# Power.net
KiCad netlist of a schematic drawn in Altium Designer
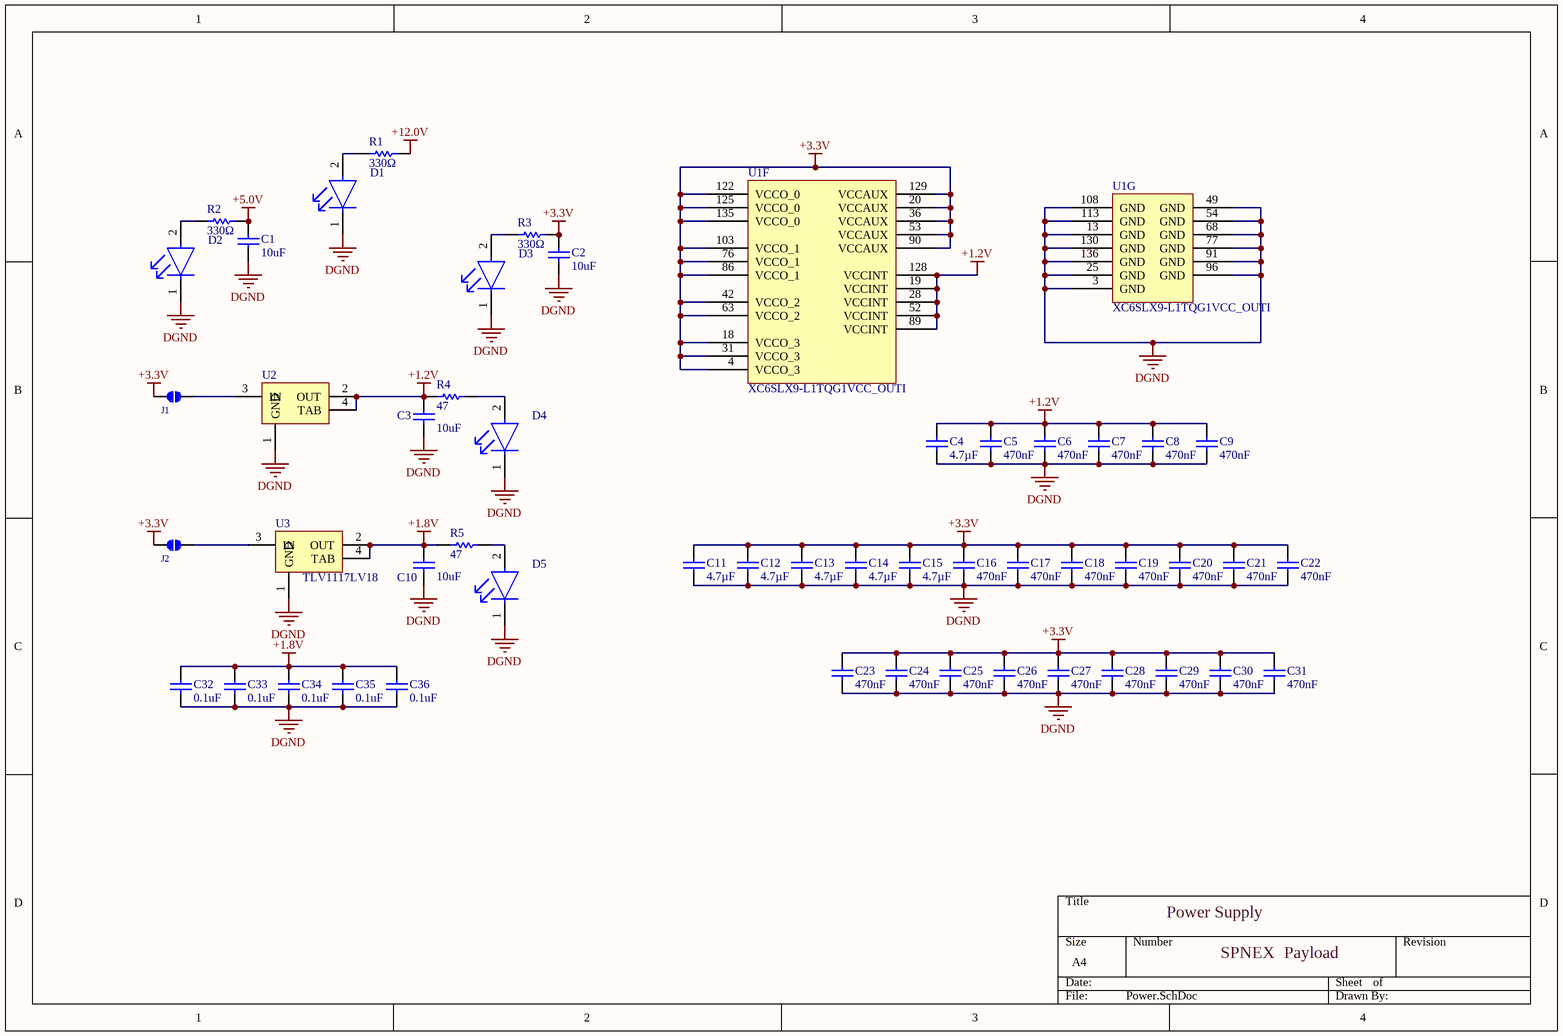
[diagram p0: Power.SchDoc]

(export (version "E")
  (design (tool "Eeschema 10.0.6"))
  (components
    (comp (ref "C1")
      (value "10uF")
      (footprint "capc3216n")
      (description "Capacitor")
      (fields (field (name "Comment") "Cap Semi"))
      (libsource (lib "SPNeX_NewPL") (part "Cap_CER_10U_10V_1206"))
    )
    (comp (ref "C2")
      (value "10uF")
      (footprint "capc3216n")
      (description "Capacitor")
      (fields (field (name "Comment") "Cap Semi"))
      (libsource (lib "SPNeX_NewPL") (part "Cap_CER_10U_10V_1206"))
    )
    (comp (ref "C3")
      (value "10uF")
      (footprint "capc3216n")
      (description "Capacitor")
      (fields (field (name "Comment") "Cap Semi"))
      (libsource (lib "SPNeX_NewPL") (part "Cap_CER_10U_10V_1206"))
    )
    (comp (ref "C4")
      (value "Cap_CER_4.7U_25V_0805")
      (footprint "0805CAP")
      (description "CAP CER 4.7UF 25V X7R 0805")
      (fields
        (field (name "MANUFACTURER") "TDK Corporation")
        (field (name "MANUFACTURER PART NUMBER") "C2012X7R1E475K125AB")
        (field (name "CAPACITANCE") "4.7µF")
      )
      (libsource (lib "SPNeX_NewPL") (part "Cap_CER_4.7U_25V_0805"))
    )
    (comp (ref "C5")
      (value "CAP CER 0.47UF 10V X7R 0603")
      (footprint "0603CAP")
      (description "0.47µF ±10% 10V Ceramic Capacitor X7R 0603 (1608 Metric)")
      (fields
        (field (name "MANUFACTURER") "KEMET")
        (field (name "MANUFACTURER PART NUMBER") "C0603C474K8RACTU")
        (field (name "CAPACITANCE") "470nF")
      )
      (libsource (lib "SPNeX_NewPL") (part "Cap_CER_0.47U_10V_0603"))
    )
    (comp (ref "C6")
      (value "CAP CER 0.47UF 10V X7R 0603")
      (footprint "0603CAP")
      (description "0.47µF ±10% 10V Ceramic Capacitor X7R 0603 (1608 Metric)")
      (fields
        (field (name "MANUFACTURER") "KEMET")
        (field (name "MANUFACTURER PART NUMBER") "C0603C474K8RACTU")
        (field (name "CAPACITANCE") "470nF")
      )
      (libsource (lib "SPNeX_NewPL") (part "Cap_CER_0.47U_10V_0603"))
    )
    (comp (ref "C7")
      (value "CAP CER 0.47UF 10V X7R 0603")
      (footprint "0603CAP")
      (description "0.47µF ±10% 10V Ceramic Capacitor X7R 0603 (1608 Metric)")
      (fields
        (field (name "MANUFACTURER") "KEMET")
        (field (name "MANUFACTURER PART NUMBER") "C0603C474K8RACTU")
        (field (name "CAPACITANCE") "470nF")
      )
      (libsource (lib "SPNeX_NewPL") (part "Cap_CER_0.47U_10V_0603"))
    )
    (comp (ref "C8")
      (value "CAP CER 0.47UF 10V X7R 0603")
      (footprint "0603CAP")
      (description "0.47µF ±10% 10V Ceramic Capacitor X7R 0603 (1608 Metric)")
      (fields
        (field (name "MANUFACTURER") "KEMET")
        (field (name "MANUFACTURER PART NUMBER") "C0603C474K8RACTU")
        (field (name "CAPACITANCE") "470nF")
      )
      (libsource (lib "SPNeX_NewPL") (part "Cap_CER_0.47U_10V_0603"))
    )
    (comp (ref "C9")
      (value "CAP CER 0.47UF 10V X7R 0603")
      (footprint "0603CAP")
      (description "0.47µF ±10% 10V Ceramic Capacitor X7R 0603 (1608 Metric)")
      (fields
        (field (name "MANUFACTURER") "KEMET")
        (field (name "MANUFACTURER PART NUMBER") "C0603C474K8RACTU")
        (field (name "CAPACITANCE") "470nF")
      )
      (libsource (lib "SPNeX_NewPL") (part "Cap_CER_0.47U_10V_0603"))
    )
    (comp (ref "C10")
      (value "10uF")
      (footprint "capc3216n")
      (description "Capacitor")
      (fields (field (name "Comment") "Cap Semi"))
      (libsource (lib "SPNeX_NewPL") (part "Cap_CER_10U_10V_1206"))
    )
    (comp (ref "C11")
      (value "Cap_CER_4.7U_25V_0805")
      (footprint "0805CAP")
      (description "CAP CER 4.7UF 25V X7R 0805")
      (fields
        (field (name "MANUFACTURER") "TDK Corporation")
        (field (name "MANUFACTURER PART NUMBER") "C2012X7R1E475K125AB")
        (field (name "CAPACITANCE") "4.7µF")
      )
      (libsource (lib "SPNeX_NewPL") (part "Cap_CER_4.7U_25V_0805"))
    )
    (comp (ref "C12")
      (value "Cap_CER_4.7U_25V_0805")
      (footprint "0805CAP")
      (description "CAP CER 4.7UF 25V X7R 0805")
      (fields
        (field (name "MANUFACTURER") "TDK Corporation")
        (field (name "MANUFACTURER PART NUMBER") "C2012X7R1E475K125AB")
        (field (name "CAPACITANCE") "4.7µF")
      )
      (libsource (lib "SPNeX_NewPL") (part "Cap_CER_4.7U_25V_0805"))
    )
    (comp (ref "C13")
      (value "Cap_CER_4.7U_25V_0805")
      (footprint "0805CAP")
      (description "CAP CER 4.7UF 25V X7R 0805")
      (fields
        (field (name "MANUFACTURER") "TDK Corporation")
        (field (name "MANUFACTURER PART NUMBER") "C2012X7R1E475K125AB")
        (field (name "CAPACITANCE") "4.7µF")
      )
      (libsource (lib "SPNeX_NewPL") (part "Cap_CER_4.7U_25V_0805"))
    )
    (comp (ref "C14")
      (value "Cap_CER_4.7U_25V_0805")
      (footprint "0805CAP")
      (description "CAP CER 4.7UF 25V X7R 0805")
      (fields
        (field (name "MANUFACTURER") "TDK Corporation")
        (field (name "MANUFACTURER PART NUMBER") "C2012X7R1E475K125AB")
        (field (name "CAPACITANCE") "4.7µF")
      )
      (libsource (lib "SPNeX_NewPL") (part "Cap_CER_4.7U_25V_0805"))
    )
    (comp (ref "C15")
      (value "Cap_CER_4.7U_25V_0805")
      (footprint "0805CAP")
      (description "CAP CER 4.7UF 25V X7R 0805")
      (fields
        (field (name "MANUFACTURER") "TDK Corporation")
        (field (name "MANUFACTURER PART NUMBER") "C2012X7R1E475K125AB")
        (field (name "CAPACITANCE") "4.7µF")
      )
      (libsource (lib "SPNeX_NewPL") (part "Cap_CER_4.7U_25V_0805"))
    )
    (comp (ref "C16")
      (value "CAP CER 0.47UF 10V X7R 0603")
      (footprint "0603CAP")
      (description "0.47µF ±10% 10V Ceramic Capacitor X7R 0603 (1608 Metric)")
      (fields
        (field (name "MANUFACTURER") "KEMET")
        (field (name "MANUFACTURER PART NUMBER") "C0603C474K8RACTU")
        (field (name "CAPACITANCE") "470nF")
      )
      (libsource (lib "SPNeX_NewPL") (part "Cap_CER_0.47U_10V_0603"))
    )
    (comp (ref "C17")
      (value "CAP CER 0.47UF 10V X7R 0603")
      (footprint "0603CAP")
      (description "0.47µF ±10% 10V Ceramic Capacitor X7R 0603 (1608 Metric)")
      (fields
        (field (name "MANUFACTURER") "KEMET")
        (field (name "MANUFACTURER PART NUMBER") "C0603C474K8RACTU")
        (field (name "CAPACITANCE") "470nF")
      )
      (libsource (lib "SPNeX_NewPL") (part "Cap_CER_0.47U_10V_0603"))
    )
    (comp (ref "C18")
      (value "CAP CER 0.47UF 10V X7R 0603")
      (footprint "0603CAP")
      (description "0.47µF ±10% 10V Ceramic Capacitor X7R 0603 (1608 Metric)")
      (fields
        (field (name "MANUFACTURER") "KEMET")
        (field (name "MANUFACTURER PART NUMBER") "C0603C474K8RACTU")
        (field (name "CAPACITANCE") "470nF")
      )
      (libsource (lib "SPNeX_NewPL") (part "Cap_CER_0.47U_10V_0603"))
    )
    (comp (ref "C19")
      (value "CAP CER 0.47UF 10V X7R 0603")
      (footprint "0603CAP")
      (description "0.47µF ±10% 10V Ceramic Capacitor X7R 0603 (1608 Metric)")
      (fields
        (field (name "MANUFACTURER") "KEMET")
        (field (name "MANUFACTURER PART NUMBER") "C0603C474K8RACTU")
        (field (name "CAPACITANCE") "470nF")
      )
      (libsource (lib "SPNeX_NewPL") (part "Cap_CER_0.47U_10V_0603"))
    )
    (comp (ref "C20")
      (value "CAP CER 0.47UF 10V X7R 0603")
      (footprint "0603CAP")
      (description "0.47µF ±10% 10V Ceramic Capacitor X7R 0603 (1608 Metric)")
      (fields
        (field (name "MANUFACTURER") "KEMET")
        (field (name "MANUFACTURER PART NUMBER") "C0603C474K8RACTU")
        (field (name "CAPACITANCE") "470nF")
      )
      (libsource (lib "SPNeX_NewPL") (part "Cap_CER_0.47U_10V_0603"))
    )
    (comp (ref "C21")
      (value "CAP CER 0.47UF 10V X7R 0603")
      (footprint "0603CAP")
      (description "0.47µF ±10% 10V Ceramic Capacitor X7R 0603 (1608 Metric)")
      (fields
        (field (name "MANUFACTURER") "KEMET")
        (field (name "MANUFACTURER PART NUMBER") "C0603C474K8RACTU")
        (field (name "CAPACITANCE") "470nF")
      )
      (libsource (lib "SPNeX_NewPL") (part "Cap_CER_0.47U_10V_0603"))
    )
    (comp (ref "C22")
      (value "CAP CER 0.47UF 10V X7R 0603")
      (footprint "0603CAP")
      (description "0.47µF ±10% 10V Ceramic Capacitor X7R 0603 (1608 Metric)")
      (fields
        (field (name "MANUFACTURER") "KEMET")
        (field (name "MANUFACTURER PART NUMBER") "C0603C474K8RACTU")
        (field (name "CAPACITANCE") "470nF")
      )
      (libsource (lib "SPNeX_NewPL") (part "Cap_CER_0.47U_10V_0603"))
    )
    (comp (ref "C23")
      (value "CAP CER 0.47UF 10V X7R 0603")
      (footprint "0603CAP")
      (description "0.47µF ±10% 10V Ceramic Capacitor X7R 0603 (1608 Metric)")
      (fields
        (field (name "MANUFACTURER") "KEMET")
        (field (name "MANUFACTURER PART NUMBER") "C0603C474K8RACTU")
        (field (name "CAPACITANCE") "470nF")
      )
      (libsource (lib "SPNeX_NewPL") (part "Cap_CER_0.47U_10V_0603"))
    )
    (comp (ref "C24")
      (value "CAP CER 0.47UF 10V X7R 0603")
      (footprint "0603CAP")
      (description "0.47µF ±10% 10V Ceramic Capacitor X7R 0603 (1608 Metric)")
      (fields
        (field (name "MANUFACTURER") "KEMET")
        (field (name "MANUFACTURER PART NUMBER") "C0603C474K8RACTU")
        (field (name "CAPACITANCE") "470nF")
      )
      (libsource (lib "SPNeX_NewPL") (part "Cap_CER_0.47U_10V_0603"))
    )
    (comp (ref "C25")
      (value "CAP CER 0.47UF 10V X7R 0603")
      (footprint "0603CAP")
      (description "0.47µF ±10% 10V Ceramic Capacitor X7R 0603 (1608 Metric)")
      (fields
        (field (name "MANUFACTURER") "KEMET")
        (field (name "MANUFACTURER PART NUMBER") "C0603C474K8RACTU")
        (field (name "CAPACITANCE") "470nF")
      )
      (libsource (lib "SPNeX_NewPL") (part "Cap_CER_0.47U_10V_0603"))
    )
    (comp (ref "C26")
      (value "CAP CER 0.47UF 10V X7R 0603")
      (footprint "0603CAP")
      (description "0.47µF ±10% 10V Ceramic Capacitor X7R 0603 (1608 Metric)")
      (fields
        (field (name "MANUFACTURER") "KEMET")
        (field (name "MANUFACTURER PART NUMBER") "C0603C474K8RACTU")
        (field (name "CAPACITANCE") "470nF")
      )
      (libsource (lib "SPNeX_NewPL") (part "Cap_CER_0.47U_10V_0603"))
    )
    (comp (ref "C27")
      (value "CAP CER 0.47UF 10V X7R 0603")
      (footprint "0603CAP")
      (description "0.47µF ±10% 10V Ceramic Capacitor X7R 0603 (1608 Metric)")
      (fields
        (field (name "MANUFACTURER") "KEMET")
        (field (name "MANUFACTURER PART NUMBER") "C0603C474K8RACTU")
        (field (name "CAPACITANCE") "470nF")
      )
      (libsource (lib "SPNeX_NewPL") (part "Cap_CER_0.47U_10V_0603"))
    )
    (comp (ref "C28")
      (value "CAP CER 0.47UF 10V X7R 0603")
      (footprint "0603CAP")
      (description "0.47µF ±10% 10V Ceramic Capacitor X7R 0603 (1608 Metric)")
      (fields
        (field (name "MANUFACTURER") "KEMET")
        (field (name "MANUFACTURER PART NUMBER") "C0603C474K8RACTU")
        (field (name "CAPACITANCE") "470nF")
      )
      (libsource (lib "SPNeX_NewPL") (part "Cap_CER_0.47U_10V_0603"))
    )
    (comp (ref "C29")
      (value "CAP CER 0.47UF 10V X7R 0603")
      (footprint "0603CAP")
      (description "0.47µF ±10% 10V Ceramic Capacitor X7R 0603 (1608 Metric)")
      (fields
        (field (name "MANUFACTURER") "KEMET")
        (field (name "MANUFACTURER PART NUMBER") "C0603C474K8RACTU")
        (field (name "CAPACITANCE") "470nF")
      )
      (libsource (lib "SPNeX_NewPL") (part "Cap_CER_0.47U_10V_0603"))
    )
    (comp (ref "C30")
      (value "CAP CER 0.47UF 10V X7R 0603")
      (footprint "0603CAP")
      (description "0.47µF ±10% 10V Ceramic Capacitor X7R 0603 (1608 Metric)")
      (fields
        (field (name "MANUFACTURER") "KEMET")
        (field (name "MANUFACTURER PART NUMBER") "C0603C474K8RACTU")
        (field (name "CAPACITANCE") "470nF")
      )
      (libsource (lib "SPNeX_NewPL") (part "Cap_CER_0.47U_10V_0603"))
    )
    (comp (ref "C31")
      (value "CAP CER 0.47UF 10V X7R 0603")
      (footprint "0603CAP")
      (description "0.47µF ±10% 10V Ceramic Capacitor X7R 0603 (1608 Metric)")
      (fields
        (field (name "MANUFACTURER") "KEMET")
        (field (name "MANUFACTURER PART NUMBER") "C0603C474K8RACTU")
        (field (name "CAPACITANCE") "470nF")
      )
      (libsource (lib "SPNeX_NewPL") (part "Cap_CER_0.47U_10V_0603"))
    )
    (comp (ref "C32")
      (value "0.1uF")
      (footprint "0805CAP")
      (description "Surface Mount Ceramic Multilayer Capacitor 0.1uF 10% X7R 16V 0805 Paper T/R")
      (fields
        (field (name "MANUFACTURER") "Yageo")
        (field (name "MANUFACTURER PART NUMBER") "CC0805KRX7R7BB104")
      )
      (libsource (lib "SPNeX_NewPL") (part "CAP_CER_0.1uf_10V_0805"))
    )
    (comp (ref "C33")
      (value "0.1uF")
      (footprint "0805CAP")
      (description "Surface Mount Ceramic Multilayer Capacitor 0.1uF 10% X7R 16V 0805 Paper T/R")
      (fields
        (field (name "MANUFACTURER") "Yageo")
        (field (name "MANUFACTURER PART NUMBER") "CC0805KRX7R7BB104")
      )
      (libsource (lib "SPNeX_NewPL") (part "CAP_CER_0.1uf_10V_0805"))
    )
    (comp (ref "C34")
      (value "0.1uF")
      (footprint "0805CAP")
      (description "Surface Mount Ceramic Multilayer Capacitor 0.1uF 10% X7R 16V 0805 Paper T/R")
      (fields
        (field (name "MANUFACTURER") "Yageo")
        (field (name "MANUFACTURER PART NUMBER") "CC0805KRX7R7BB104")
      )
      (libsource (lib "SPNeX_NewPL") (part "CAP_CER_0.1uf_10V_0805"))
    )
    (comp (ref "C35")
      (value "0.1uF")
      (footprint "0805CAP")
      (description "Surface Mount Ceramic Multilayer Capacitor 0.1uF 10% X7R 16V 0805 Paper T/R")
      (fields
        (field (name "MANUFACTURER") "Yageo")
        (field (name "MANUFACTURER PART NUMBER") "CC0805KRX7R7BB104")
      )
      (libsource (lib "SPNeX_NewPL") (part "CAP_CER_0.1uf_10V_0805"))
    )
    (comp (ref "C36")
      (value "0.1uF")
      (footprint "0805CAP")
      (description "Surface Mount Ceramic Multilayer Capacitor 0.1uF 10% X7R 16V 0805 Paper T/R")
      (fields
        (field (name "MANUFACTURER") "Yageo")
        (field (name "MANUFACTURER PART NUMBER") "CC0805KRX7R7BB104")
      )
      (libsource (lib "SPNeX_NewPL") (part "CAP_CER_0.1uf_10V_0805"))
    )
    (comp (ref "D1")
      (value "LED RED CLEAR 2SMD")
      (footprint "ROHM_SML-21_MFG")
      (description "Red 625nm LED Indication - Discrete 1.8V 0805 (2012 Metric)")
      (fields
        (field (name "MANUFACTURER") "Kingbright")
        (field (name "MANUFACTURER PART NUMBER") "APT2012LSECK/J3-PRV")
      )
      (libsource (lib "SPNeX_NewPL") (part "APT2012LSECK/J3-PRV"))
    )
    (comp (ref "D2")
      (value "LED RED CLEAR 2SMD")
      (footprint "ROHM_SML-21_MFG")
      (description "Red 625nm LED Indication - Discrete 1.8V 0805 (2012 Metric)")
      (fields
        (field (name "MANUFACTURER") "Kingbright")
        (field (name "MANUFACTURER PART NUMBER") "APT2012LSECK/J3-PRV")
      )
      (libsource (lib "SPNeX_NewPL") (part "APT2012LSECK/J3-PRV"))
    )
    (comp (ref "D3")
      (value "LED RED CLEAR 2SMD")
      (footprint "ROHM_SML-21_MFG")
      (description "Red 625nm LED Indication - Discrete 1.8V 0805 (2012 Metric)")
      (fields
        (field (name "MANUFACTURER") "Kingbright")
        (field (name "MANUFACTURER PART NUMBER") "APT2012LSECK/J3-PRV")
      )
      (libsource (lib "SPNeX_NewPL") (part "APT2012LSECK/J3-PRV"))
    )
    (comp (ref "D4")
      (value "LED RED CLEAR 2SMD")
      (footprint "ROHM_SML-21_MFG")
      (description "Red 625nm LED Indication - Discrete 1.8V 0805 (2012 Metric)")
      (fields
        (field (name "MANUFACTURER") "Kingbright")
        (field (name "MANUFACTURER PART NUMBER") "APT2012LSECK/J3-PRV")
      )
      (libsource (lib "SPNeX_NewPL") (part "APT2012LSECK/J3-PRV"))
    )
    (comp (ref "D5")
      (value "LED RED CLEAR 2SMD")
      (footprint "ROHM_SML-21_MFG")
      (description "Red 625nm LED Indication - Discrete 1.8V 0805 (2012 Metric)")
      (fields
        (field (name "MANUFACTURER") "Kingbright")
        (field (name "MANUFACTURER PART NUMBER") "APT2012LSECK/J3-PRV")
      )
      (libsource (lib "SPNeX_NewPL") (part "APT2012LSECK/J3-PRV"))
    )
    (comp (ref "J1")
      (value "JUMPER")
      (footprint "SJMP")
      (description "OPTION SELECTION PAD")
      (libsource (lib "Spnex_lib") (part "JUMPER"))
    )
    (comp (ref "J2")
      (value "JUMPER")
      (footprint "SJMP")
      (description "OPTION SELECTION PAD")
      (libsource (lib "Spnex_lib") (part "JUMPER"))
    )
    (comp (ref "R1")
      (value "RES_330 Ohm_0603")
      (footprint "0603")
      (description "Res Thick Film 0603 330 Ohm 5% 0.1W(1/10W) +/-200ppm/ßC Pad SMD Automotive T/R")
      (fields
        (field (name "MANUFACTURER") "Panasonic")
        (field (name "MANUFACTURER PART NUMBER") "ERJ-3GEYJ331V")
        (field (name "RESISTANCE") "330Ω")
      )
      (libsource (lib "Spnex_lib") (part "RES_330 Ohm_0603"))
    )
    (comp (ref "R2")
      (value "RES_330 Ohm_0603")
      (footprint "0603")
      (description "Res Thick Film 0603 330 Ohm 5% 0.1W(1/10W) +/-200ppm/ßC Pad SMD Automotive T/R")
      (fields
        (field (name "MANUFACTURER") "Panasonic")
        (field (name "MANUFACTURER PART NUMBER") "ERJ-3GEYJ331V")
        (field (name "RESISTANCE") "330Ω")
      )
      (libsource (lib "Spnex_lib") (part "RES_330 Ohm_0603"))
    )
    (comp (ref "R3")
      (value "RES_330 Ohm_0603")
      (footprint "0603")
      (description "Res Thick Film 0603 330 Ohm 5% 0.1W(1/10W) +/-200ppm/ßC Pad SMD Automotive T/R")
      (fields
        (field (name "MANUFACTURER") "Panasonic")
        (field (name "MANUFACTURER PART NUMBER") "ERJ-3GEYJ331V")
        (field (name "RESISTANCE") "330Ω")
      )
      (libsource (lib "Spnex_lib") (part "RES_330 Ohm_0603"))
    )
    (comp (ref "R4")
      (value "RES_47R_0.25W_0805")
      (footprint "0603RES")
      (description "RES SMD 47 OHM 5% 0.4W 0805")
      (fields
        (field (name "MANUFACTURER") "Rohm Semiconductor")
        (field (name "MANUFACTURER PART NUMBER") "ESR10EZPJ470")
        (field (name "RESISTANCE (OHMS)") "47")
      )
      (libsource (lib "SPNeX_NewPL") (part "RES_47R_0.25W_0805"))
    )
    (comp (ref "R5")
      (value "RES_47R_0.25W_0805")
      (footprint "0603RES")
      (description "RES SMD 47 OHM 5% 0.4W 0805")
      (fields
        (field (name "MANUFACTURER") "Rohm Semiconductor")
        (field (name "MANUFACTURER PART NUMBER") "ESR10EZPJ470")
        (field (name "RESISTANCE (OHMS)") "47")
      )
      (libsource (lib "SPNeX_NewPL") (part "RES_47R_0.25W_0805"))
    )
    (comp (ref "U1")
      (value "XC6SLX9-L1TQG1VCC_OUTI")
      (footprint "TQG144_M")
      (fields (field (name "PUBLISHER") "Altium Limited"))
      (libsource (lib "SPNeX_NewPL") (part "XC6SLX9-L1TQG144I"))
    )
    (comp (ref "U2")
      (value "IC REG LINEAR 1.2V 1A SOT223-4")
      (footprint "DCY0004A_M")
      (description "Linear Voltage Regulator IC Positive Fixed 1 Output 1.2V 1A SOT-223-4")
      (fields
        (field (name "MANUFACTURER") "Texas Instruments")
        (field (name "MANUFACTURER PART NUMBER") "TLV1117LV12DCYR")
      )
      (libsource (lib "SPNeX_NewPL") (part "TLV1117LV12DCYR"))
    )
    (comp (ref "U3")
      (value "TLV1117LV18")
      (footprint "DCY0004A_M")
      (description "1A Low-Dropout Linear Regulator, 4-pin SOT-223")
      (fields
        (field (name "MANUFACTURER") "Texas Instruments")
        (field (name "MANUFACTURER PART NUMBER") "TLV1117LV18DCYR")
      )
      (libsource (lib "SPNeX_NewPL") (part "TLV1117LV18"))
    )
  )
  (nets
    (net (code "1") (name "+1.2V") (class "Default")
      (node (ref "C3") (pin "2") (pinfunction "2_2") (pintype "passive"))
      (node (ref "C4") (pin "1") (pinfunction "1_1") (pintype "passive"))
      (node (ref "C5") (pin "1") (pinfunction "1_1") (pintype "passive"))
      (node (ref "C6") (pin "1") (pinfunction "1_1") (pintype "passive"))
      (node (ref "C7") (pin "1") (pinfunction "1_1") (pintype "passive"))
      (node (ref "C8") (pin "1") (pinfunction "1_1") (pintype "passive"))
      (node (ref "C9") (pin "1") (pinfunction "1_1") (pintype "passive"))
      (node (ref "R4") (pin "1") (pinfunction "1_1") (pintype "passive"))
      (node (ref "U1") (pin "128") (pinfunction "VCCINT_128") (pintype "power_in"))
      (node (ref "U1") (pin "19") (pinfunction "VCCINT_19") (pintype "power_in"))
      (node (ref "U1") (pin "28") (pinfunction "VCCINT_28") (pintype "power_in"))
      (node (ref "U1") (pin "52") (pinfunction "VCCINT_52") (pintype "power_in"))
      (node (ref "U1") (pin "89") (pinfunction "VCCINT_89") (pintype "power_in"))
      (node (ref "U2") (pin "2") (pinfunction "OUT_2") (pintype "power_in"))
      (node (ref "U2") (pin "4") (pinfunction "TAB_4") (pintype "power_in"))
    )
    (net (code "2") (name "+1.8V") (class "Default")
      (node (ref "C10") (pin "2") (pinfunction "2_2") (pintype "passive"))
      (node (ref "C32") (pin "2") (pinfunction "2_2") (pintype "passive"))
      (node (ref "C33") (pin "2") (pinfunction "2_2") (pintype "passive"))
      (node (ref "C34") (pin "2") (pinfunction "2_2") (pintype "passive"))
      (node (ref "C35") (pin "2") (pinfunction "2_2") (pintype "passive"))
      (node (ref "C36") (pin "2") (pinfunction "2_2") (pintype "passive"))
      (node (ref "R5") (pin "1") (pinfunction "1_1") (pintype "passive"))
      (node (ref "U3") (pin "2") (pinfunction "OUT_2") (pintype "power_in"))
      (node (ref "U3") (pin "4") (pinfunction "TAB_4") (pintype "power_in"))
    )
    (net (code "3") (name "+3.3V") (class "Default")
      (node (ref "C11") (pin "1") (pinfunction "1_1") (pintype "passive"))
      (node (ref "C12") (pin "1") (pinfunction "1_1") (pintype "passive"))
      (node (ref "C13") (pin "1") (pinfunction "1_1") (pintype "passive"))
      (node (ref "C14") (pin "1") (pinfunction "1_1") (pintype "passive"))
      (node (ref "C15") (pin "1") (pinfunction "1_1") (pintype "passive"))
      (node (ref "C16") (pin "1") (pinfunction "1_1") (pintype "passive"))
      (node (ref "C17") (pin "1") (pinfunction "1_1") (pintype "passive"))
      (node (ref "C18") (pin "1") (pinfunction "1_1") (pintype "passive"))
      (node (ref "C19") (pin "1") (pinfunction "1_1") (pintype "passive"))
      (node (ref "C2") (pin "2") (pinfunction "2_2") (pintype "passive"))
      (node (ref "C20") (pin "1") (pinfunction "1_1") (pintype "passive"))
      (node (ref "C21") (pin "1") (pinfunction "1_1") (pintype "passive"))
      (node (ref "C22") (pin "1") (pinfunction "1_1") (pintype "passive"))
      (node (ref "C23") (pin "1") (pinfunction "1_1") (pintype "passive"))
      (node (ref "C24") (pin "1") (pinfunction "1_1") (pintype "passive"))
      (node (ref "C25") (pin "1") (pinfunction "1_1") (pintype "passive"))
      (node (ref "C26") (pin "1") (pinfunction "1_1") (pintype "passive"))
      (node (ref "C27") (pin "1") (pinfunction "1_1") (pintype "passive"))
      (node (ref "C28") (pin "1") (pinfunction "1_1") (pintype "passive"))
      (node (ref "C29") (pin "1") (pinfunction "1_1") (pintype "passive"))
      (node (ref "C30") (pin "1") (pinfunction "1_1") (pintype "passive"))
      (node (ref "C31") (pin "1") (pinfunction "1_1") (pintype "passive"))
      (node (ref "J1") (pin "1") (pinfunction "1_1") (pintype "passive"))
      (node (ref "J2") (pin "1") (pinfunction "1_1") (pintype "passive"))
      (node (ref "R3") (pin "2") (pinfunction "2_2") (pintype "passive"))
      (node (ref "U1") (pin "103") (pinfunction "VCCO_1_103") (pintype "power_in"))
      (node (ref "U1") (pin "122") (pinfunction "VCCO_0_122") (pintype "power_in"))
      (node (ref "U1") (pin "125") (pinfunction "VCCO_0_125") (pintype "power_in"))
      (node (ref "U1") (pin "129") (pinfunction "VCCAUX_129") (pintype "power_in"))
      (node (ref "U1") (pin "135") (pinfunction "VCCO_0_135") (pintype "power_in"))
      (node (ref "U1") (pin "18") (pinfunction "VCCO_3_18") (pintype "power_in"))
      (node (ref "U1") (pin "20") (pinfunction "VCCAUX_20") (pintype "power_in"))
      (node (ref "U1") (pin "31") (pinfunction "VCCO_3_31") (pintype "power_in"))
      (node (ref "U1") (pin "36") (pinfunction "VCCAUX_36") (pintype "power_in"))
      (node (ref "U1") (pin "4") (pinfunction "VCCO_3_4") (pintype "power_in"))
      (node (ref "U1") (pin "42") (pinfunction "VCCO_2_42") (pintype "power_in"))
      (node (ref "U1") (pin "53") (pinfunction "VCCAUX_53") (pintype "power_in"))
      (node (ref "U1") (pin "63") (pinfunction "VCCO_2_63") (pintype "power_in"))
      (node (ref "U1") (pin "76") (pinfunction "VCCO_1_76") (pintype "power_in"))
      (node (ref "U1") (pin "86") (pinfunction "VCCO_1_86") (pintype "power_in"))
      (node (ref "U1") (pin "90") (pinfunction "VCCAUX_90") (pintype "power_in"))
    )
    (net (code "4") (name "+5.0V") (class "Default")
      (node (ref "C1") (pin "2") (pinfunction "2_2") (pintype "passive"))
      (node (ref "R2") (pin "2") (pinfunction "2_2") (pintype "passive"))
    )
    (net (code "5") (name "+12.0V") (class "Default")
      (node (ref "R1") (pin "2") (pinfunction "2_2") (pintype "passive"))
    )
    (net (code "6") (name "DGND") (class "Default")
      (node (ref "C1") (pin "1") (pinfunction "1_1") (pintype "passive"))
      (node (ref "C10") (pin "1") (pinfunction "1_1") (pintype "passive"))
      (node (ref "C11") (pin "2") (pinfunction "2_2") (pintype "passive"))
      (node (ref "C12") (pin "2") (pinfunction "2_2") (pintype "passive"))
      (node (ref "C13") (pin "2") (pinfunction "2_2") (pintype "passive"))
      (node (ref "C14") (pin "2") (pinfunction "2_2") (pintype "passive"))
      (node (ref "C15") (pin "2") (pinfunction "2_2") (pintype "passive"))
      (node (ref "C16") (pin "2") (pinfunction "2_2") (pintype "passive"))
      (node (ref "C17") (pin "2") (pinfunction "2_2") (pintype "passive"))
      (node (ref "C18") (pin "2") (pinfunction "2_2") (pintype "passive"))
      (node (ref "C19") (pin "2") (pinfunction "2_2") (pintype "passive"))
      (node (ref "C2") (pin "1") (pinfunction "1_1") (pintype "passive"))
      (node (ref "C20") (pin "2") (pinfunction "2_2") (pintype "passive"))
      (node (ref "C21") (pin "2") (pinfunction "2_2") (pintype "passive"))
      (node (ref "C22") (pin "2") (pinfunction "2_2") (pintype "passive"))
      (node (ref "C23") (pin "2") (pinfunction "2_2") (pintype "passive"))
      (node (ref "C24") (pin "2") (pinfunction "2_2") (pintype "passive"))
      (node (ref "C25") (pin "2") (pinfunction "2_2") (pintype "passive"))
      (node (ref "C26") (pin "2") (pinfunction "2_2") (pintype "passive"))
      (node (ref "C27") (pin "2") (pinfunction "2_2") (pintype "passive"))
      (node (ref "C28") (pin "2") (pinfunction "2_2") (pintype "passive"))
      (node (ref "C29") (pin "2") (pinfunction "2_2") (pintype "passive"))
      (node (ref "C3") (pin "1") (pinfunction "1_1") (pintype "passive"))
      (node (ref "C30") (pin "2") (pinfunction "2_2") (pintype "passive"))
      (node (ref "C31") (pin "2") (pinfunction "2_2") (pintype "passive"))
      (node (ref "C32") (pin "1") (pinfunction "1_1") (pintype "passive"))
      (node (ref "C33") (pin "1") (pinfunction "1_1") (pintype "passive"))
      (node (ref "C34") (pin "1") (pinfunction "1_1") (pintype "passive"))
      (node (ref "C35") (pin "1") (pinfunction "1_1") (pintype "passive"))
      (node (ref "C36") (pin "1") (pinfunction "1_1") (pintype "passive"))
      (node (ref "C4") (pin "2") (pinfunction "2_2") (pintype "passive"))
      (node (ref "C5") (pin "2") (pinfunction "2_2") (pintype "passive"))
      (node (ref "C6") (pin "2") (pinfunction "2_2") (pintype "passive"))
      (node (ref "C7") (pin "2") (pinfunction "2_2") (pintype "passive"))
      (node (ref "C8") (pin "2") (pinfunction "2_2") (pintype "passive"))
      (node (ref "C9") (pin "2") (pinfunction "2_2") (pintype "passive"))
      (node (ref "D1") (pin "1") (pinfunction "C_1") (pintype "passive"))
      (node (ref "D2") (pin "1") (pinfunction "C_1") (pintype "passive"))
      (node (ref "D3") (pin "1") (pinfunction "C_1") (pintype "passive"))
      (node (ref "D4") (pin "1") (pinfunction "C_1") (pintype "passive"))
      (node (ref "D5") (pin "1") (pinfunction "C_1") (pintype "passive"))
      (node (ref "U1") (pin "108") (pinfunction "GND_108") (pintype "power_in"))
      (node (ref "U1") (pin "113") (pinfunction "GND_113") (pintype "power_in"))
      (node (ref "U1") (pin "13") (pinfunction "GND_13") (pintype "power_in"))
      (node (ref "U1") (pin "130") (pinfunction "GND_130") (pintype "power_in"))
      (node (ref "U1") (pin "136") (pinfunction "GND_136") (pintype "power_in"))
      (node (ref "U1") (pin "25") (pinfunction "GND_25") (pintype "power_in"))
      (node (ref "U1") (pin "3") (pinfunction "GND_3") (pintype "power_in"))
      (node (ref "U1") (pin "49") (pinfunction "GND_49") (pintype "power_in"))
      (node (ref "U1") (pin "54") (pinfunction "GND_54") (pintype "power_in"))
      (node (ref "U1") (pin "68") (pinfunction "GND_68") (pintype "power_in"))
      (node (ref "U1") (pin "77") (pinfunction "GND_77") (pintype "power_in"))
      (node (ref "U1") (pin "91") (pinfunction "GND_91") (pintype "power_in"))
      (node (ref "U1") (pin "96") (pinfunction "GND_96") (pintype "power_in"))
      (node (ref "U2") (pin "1") (pinfunction "GND_1") (pintype "power_in"))
      (node (ref "U3") (pin "1") (pinfunction "GND_1") (pintype "power_in"))
    )
    (net (code "7") (name "Net-(D1-A)") (class "Default")
      (node (ref "D1") (pin "2") (pinfunction "A_2") (pintype "passive"))
      (node (ref "R1") (pin "1") (pinfunction "1_1") (pintype "passive"))
    )
    (net (code "8") (name "Net-(D2-A)") (class "Default")
      (node (ref "D2") (pin "2") (pinfunction "A_2") (pintype "passive"))
      (node (ref "R2") (pin "1") (pinfunction "1_1") (pintype "passive"))
    )
    (net (code "9") (name "Net-(D3-A)") (class "Default")
      (node (ref "D3") (pin "2") (pinfunction "A_2") (pintype "passive"))
      (node (ref "R3") (pin "1") (pinfunction "1_1") (pintype "passive"))
    )
    (net (code "10") (name "Net-(D4-A)") (class "Default")
      (node (ref "D4") (pin "2") (pinfunction "A_2") (pintype "passive"))
      (node (ref "R4") (pin "2") (pinfunction "2_2") (pintype "passive"))
    )
    (net (code "11") (name "Net-(D5-A)") (class "Default")
      (node (ref "D5") (pin "2") (pinfunction "A_2") (pintype "passive"))
      (node (ref "R5") (pin "2") (pinfunction "2_2") (pintype "passive"))
    )
    (net (code "12") (name "Net-(U2-IN)") (class "Default")
      (node (ref "J1") (pin "2") (pinfunction "2_2") (pintype "passive"))
      (node (ref "U2") (pin "3") (pinfunction "IN_3") (pintype "power_in"))
    )
    (net (code "13") (name "Net-(U3-IN)") (class "Default")
      (node (ref "J2") (pin "2") (pinfunction "2_2") (pintype "passive"))
      (node (ref "U3") (pin "3") (pinfunction "IN_3") (pintype "power_in"))
    )
  )
)
